# 10-Power.net
KiCad netlist of a schematic drawn in Altium Designer
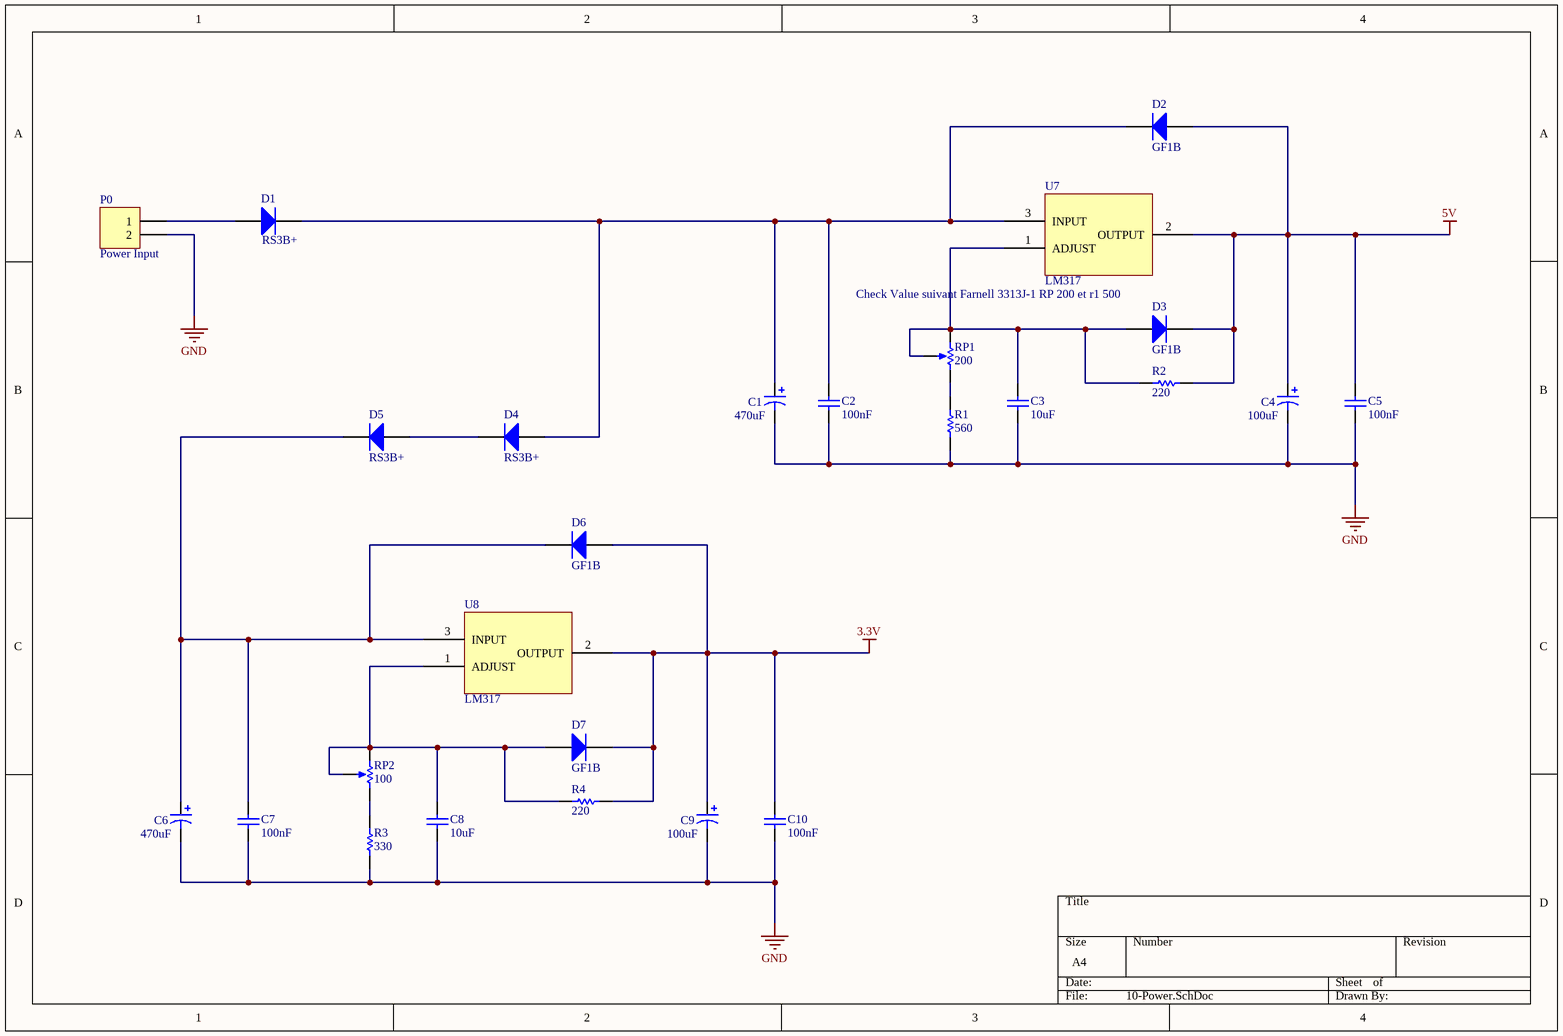
[diagram p0: 10-Power.SchDoc]

(export (version "E")
  (design (tool "Eeschema 10.0.6"))
  (components
    (comp (ref "C1")
      (value "470uF")
      (footprint "CAPA PANA SIZE D*")
      (description "Polarized Capacitor (Radial)")
      (libsource (lib "Miscellaneous Devices") (part "Cap Pol1"))
    )
    (comp (ref "C2")
      (value "100nF")
      (footprint "capa 1206")
      (description "Capacitor")
      (libsource (lib "Miscellaneous Devices") (part "Cap"))
    )
    (comp (ref "C3")
      (value "10uF")
      (footprint "capa 1206")
      (description "Capacitor")
      (libsource (lib "Miscellaneous Devices") (part "Cap"))
    )
    (comp (ref "C4")
      (value "100uF")
      (footprint "CAPA PANA SIZE D*")
      (description "Polarized Capacitor (Radial)")
      (libsource (lib "Miscellaneous Devices") (part "Cap Pol1"))
    )
    (comp (ref "C5")
      (value "100nF")
      (footprint "capa 1206")
      (description "Capacitor")
      (libsource (lib "Miscellaneous Devices") (part "Cap"))
    )
    (comp (ref "C6")
      (value "470uF")
      (footprint "CAPA PANA SIZE D*")
      (description "Polarized Capacitor (Radial)")
      (libsource (lib "Miscellaneous Devices") (part "Cap Pol1"))
    )
    (comp (ref "C7")
      (value "100nF")
      (footprint "capa 1206")
      (description "Capacitor")
      (libsource (lib "Miscellaneous Devices") (part "Cap"))
    )
    (comp (ref "C8")
      (value "10uF")
      (footprint "capa 1206")
      (description "Capacitor")
      (libsource (lib "Miscellaneous Devices") (part "Cap"))
    )
    (comp (ref "C9")
      (value "100uF")
      (footprint "CAPA PANA SIZE D*")
      (description "Polarized Capacitor (Radial)")
      (libsource (lib "Miscellaneous Devices") (part "Cap Pol1"))
    )
    (comp (ref "C10")
      (value "100nF")
      (footprint "capa 1206")
      (description "Capacitor")
      (libsource (lib "Miscellaneous Devices") (part "Cap"))
    )
    (comp (ref "D1")
      (value "RS3B+")
      (footprint "SMC Vishay")
      (description "Default Diode")
      (libsource (lib "Miscellaneous Devices") (part "Diode"))
    )
    (comp (ref "D2")
      (value "GF1B")
      (footprint "DO-214AC(SMA)")
      (description "Default Diode")
      (libsource (lib "Miscellaneous Devices") (part "Diode"))
    )
    (comp (ref "D3")
      (value "GF1B")
      (footprint "DO-214AC(SMA)")
      (description "Default Diode")
      (libsource (lib "Miscellaneous Devices") (part "Diode"))
    )
    (comp (ref "D4")
      (value "RS3B+")
      (footprint "SMC Vishay")
      (description "Default Diode")
      (libsource (lib "Miscellaneous Devices") (part "Diode"))
    )
    (comp (ref "D5")
      (value "RS3B+")
      (footprint "SMC Vishay")
      (description "Default Diode")
      (libsource (lib "Miscellaneous Devices") (part "Diode"))
    )
    (comp (ref "D6")
      (value "GF1B")
      (footprint "DO-214AC(SMA)")
      (description "Default Diode")
      (libsource (lib "Miscellaneous Devices") (part "Diode"))
    )
    (comp (ref "D7")
      (value "GF1B")
      (footprint "DO-214AC(SMA)")
      (description "Default Diode")
      (libsource (lib "Miscellaneous Devices") (part "Diode"))
    )
    (comp (ref "P0")
      (value "Power Input")
      (footprint "PWR")
      (description "Header, 2-Pin")
      (libsource (lib "Miscellaneous Connectors") (part "Header 2"))
    )
    (comp (ref "R1")
      (value "560")
      (footprint "RES 1206")
      (description "Resistor")
      (libsource (lib "Miscellaneous Devices") (part "Res1"))
    )
    (comp (ref "R2")
      (value "220")
      (footprint "RES 1206")
      (description "Resistor")
      (libsource (lib "Miscellaneous Devices") (part "Res1"))
    )
    (comp (ref "R3")
      (value "330")
      (footprint "RES 1206")
      (description "Resistor")
      (libsource (lib "Miscellaneous Devices") (part "Res1"))
    )
    (comp (ref "R4")
      (value "220")
      (footprint "RES 1206")
      (description "Resistor")
      (libsource (lib "Miscellaneous Devices") (part "Res1"))
    )
    (comp (ref "RP1")
      (value "200")
      (footprint "3313J-1")
      (description "Potentiometer")
      (libsource (lib "Miscellaneous Devices") (part "RPot"))
    )
    (comp (ref "RP2")
      (value "100")
      (footprint "3313J-1")
      (description "Potentiometer")
      (libsource (lib "Miscellaneous Devices") (part "RPot"))
    )
    (comp (ref "U7") (value "LM317") (footprint "D2PAK") (libsource (lib "0x2a002a") (part "LM317")))
    (comp (ref "U8") (value "LM317") (footprint "D2PAK") (libsource (lib "0x2a002a") (part "LM317")))
  )
  (nets
    (net (code "1") (name "3.3V") (class "Default")
      (node (ref "C10") (pin "2") (pinfunction "2_2") (pintype "passive"))
      (node (ref "C9") (pin "1") (pinfunction "1_1") (pintype "passive"))
      (node (ref "D6") (pin "1") (pinfunction "A_1") (pintype "passive"))
      (node (ref "D7") (pin "2") (pinfunction "K_2") (pintype "passive"))
      (node (ref "R4") (pin "1") (pinfunction "1_1") (pintype "passive"))
      (node (ref "U8") (pin "2") (pinfunction "OUTPUT_2") (pintype "power_in"))
    )
    (net (code "2") (name "5V") (class "Default")
      (node (ref "C4") (pin "1") (pinfunction "1_1") (pintype "passive"))
      (node (ref "C5") (pin "2") (pinfunction "2_2") (pintype "passive"))
      (node (ref "D2") (pin "1") (pinfunction "A_1") (pintype "passive"))
      (node (ref "D3") (pin "2") (pinfunction "K_2") (pintype "passive"))
      (node (ref "R2") (pin "1") (pinfunction "1_1") (pintype "passive"))
      (node (ref "U7") (pin "2") (pinfunction "OUTPUT_2") (pintype "power_in"))
    )
    (net (code "3") (name "GND") (class "Default")
      (node (ref "C1") (pin "2") (pinfunction "2_2") (pintype "passive"))
      (node (ref "C10") (pin "1") (pinfunction "1_1") (pintype "passive"))
      (node (ref "C2") (pin "1") (pinfunction "1_1") (pintype "passive"))
      (node (ref "C3") (pin "1") (pinfunction "1_1") (pintype "passive"))
      (node (ref "C4") (pin "2") (pinfunction "2_2") (pintype "passive"))
      (node (ref "C5") (pin "1") (pinfunction "1_1") (pintype "passive"))
      (node (ref "C6") (pin "2") (pinfunction "2_2") (pintype "passive"))
      (node (ref "C7") (pin "1") (pinfunction "1_1") (pintype "passive"))
      (node (ref "C8") (pin "1") (pinfunction "1_1") (pintype "passive"))
      (node (ref "C9") (pin "2") (pinfunction "2_2") (pintype "passive"))
      (node (ref "P0") (pin "2") (pinfunction "2_2") (pintype "passive"))
      (node (ref "R1") (pin "1") (pinfunction "1_1") (pintype "passive"))
      (node (ref "R3") (pin "2") (pinfunction "2_2") (pintype "passive"))
    )
    (net (code "4") (name "Net-(D1-A)") (class "Default")
      (node (ref "D1") (pin "1") (pinfunction "A_1") (pintype "passive"))
      (node (ref "P0") (pin "1") (pinfunction "1_1") (pintype "passive"))
    )
    (net (code "5") (name "Net-(D1-K)") (class "Default")
      (node (ref "C1") (pin "1") (pinfunction "1_1") (pintype "passive"))
      (node (ref "C2") (pin "2") (pinfunction "2_2") (pintype "passive"))
      (node (ref "D1") (pin "2") (pinfunction "K_2") (pintype "passive"))
      (node (ref "D2") (pin "2") (pinfunction "K_2") (pintype "passive"))
      (node (ref "D4") (pin "1") (pinfunction "A_1") (pintype "passive"))
      (node (ref "U7") (pin "3") (pinfunction "INPUT_3") (pintype "power_in"))
    )
    (net (code "6") (name "Net-(D3-A)") (class "Default")
      (node (ref "C3") (pin "2") (pinfunction "2_2") (pintype "passive"))
      (node (ref "D3") (pin "1") (pinfunction "A_1") (pintype "passive"))
      (node (ref "R2") (pin "2") (pinfunction "2_2") (pintype "passive"))
      (node (ref "RP1") (pin "1") (pinfunction "TOP_1") (pintype "passive"))
      (node (ref "RP1") (pin "3") (pinfunction "TAP_3") (pintype "passive"))
      (node (ref "U7") (pin "1") (pinfunction "ADJUST_1") (pintype "power_in"))
    )
    (net (code "7") (name "Net-(D4-K)") (class "Default")
      (node (ref "D4") (pin "2") (pinfunction "K_2") (pintype "passive"))
      (node (ref "D5") (pin "1") (pinfunction "A_1") (pintype "passive"))
    )
    (net (code "8") (name "Net-(D5-K)") (class "Default")
      (node (ref "C6") (pin "1") (pinfunction "1_1") (pintype "passive"))
      (node (ref "C7") (pin "2") (pinfunction "2_2") (pintype "passive"))
      (node (ref "D5") (pin "2") (pinfunction "K_2") (pintype "passive"))
      (node (ref "D6") (pin "2") (pinfunction "K_2") (pintype "passive"))
      (node (ref "U8") (pin "3") (pinfunction "INPUT_3") (pintype "power_in"))
    )
    (net (code "9") (name "Net-(D7-A)") (class "Default")
      (node (ref "C8") (pin "2") (pinfunction "2_2") (pintype "passive"))
      (node (ref "D7") (pin "1") (pinfunction "A_1") (pintype "passive"))
      (node (ref "R4") (pin "2") (pinfunction "2_2") (pintype "passive"))
      (node (ref "RP2") (pin "1") (pinfunction "TOP_1") (pintype "passive"))
      (node (ref "RP2") (pin "3") (pinfunction "TAP_3") (pintype "passive"))
      (node (ref "U8") (pin "1") (pinfunction "ADJUST_1") (pintype "power_in"))
    )
    (net (code "10") (name "Net-(RP1-BOT)") (class "Default")
      (node (ref "R1") (pin "2") (pinfunction "2_2") (pintype "passive"))
      (node (ref "RP1") (pin "2") (pinfunction "BOT_2") (pintype "passive"))
    )
    (net (code "11") (name "Net-(RP2-BOT)") (class "Default")
      (node (ref "R3") (pin "1") (pinfunction "1_1") (pintype "passive"))
      (node (ref "RP2") (pin "2") (pinfunction "BOT_2") (pintype "passive"))
    )
  )
)
